# pocopin.net
KiCad netlist of a schematic drawn in Altium Designer
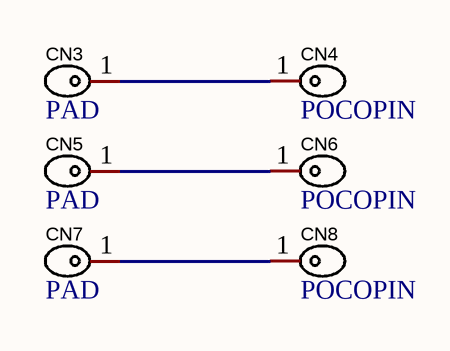
[diagram p0: pocopin.SchDoc]

(export (version "E")
  (design (tool "Eeschema 10.0.6"))
  (components
    (comp (ref "CN3")
      (value "PAD")
      (footprint "PAD")
      (fields (field (name "MANUFACTURER") "YIYUAN(怡远)") (field (name "MANUFACTURER PART") "YTC1P-3015-01"))
      (libsource (lib "Schlib1") (part "PAD"))
    )
    (comp (ref "CN4")
      (value "POCOPIN")
      (footprint "pocopin焊盘")
      (fields (field (name "MANUFACTURER") "YIYUAN(怡远)") (field (name "MANUFACTURER PART") "YTC1P-3015-01"))
      (libsource (lib "Schlib1") (part "POCOPIN"))
    )
    (comp (ref "CN5")
      (value "PAD")
      (footprint "PAD")
      (fields (field (name "MANUFACTURER") "YIYUAN(怡远)") (field (name "MANUFACTURER PART") "YTC1P-3015-01"))
      (libsource (lib "Schlib1") (part "PAD"))
    )
    (comp (ref "CN6")
      (value "POCOPIN")
      (footprint "pocopin焊盘")
      (fields (field (name "MANUFACTURER") "YIYUAN(怡远)") (field (name "MANUFACTURER PART") "YTC1P-3015-01"))
      (libsource (lib "Schlib1") (part "POCOPIN"))
    )
    (comp (ref "CN7")
      (value "PAD")
      (footprint "PAD")
      (fields (field (name "MANUFACTURER") "YIYUAN(怡远)") (field (name "MANUFACTURER PART") "YTC1P-3015-01"))
      (libsource (lib "Schlib1") (part "PAD"))
    )
    (comp (ref "CN8")
      (value "POCOPIN")
      (footprint "pocopin焊盘")
      (fields (field (name "MANUFACTURER") "YIYUAN(怡远)") (field (name "MANUFACTURER PART") "YTC1P-3015-01"))
      (libsource (lib "Schlib1") (part "POCOPIN"))
    )
  )
  (nets
    (net (code "1") (name "Net-(CN3-Pad1)") (class "Default")
      (node (ref "CN3") (pin "1") (pinfunction "1_1") (pintype "passive"))
      (node (ref "CN4") (pin "1") (pinfunction "1_1") (pintype "passive"))
    )
    (net (code "2") (name "Net-(CN5-Pad1)") (class "Default")
      (node (ref "CN5") (pin "1") (pinfunction "1_1") (pintype "passive"))
      (node (ref "CN6") (pin "1") (pinfunction "1_1") (pintype "passive"))
    )
    (net (code "3") (name "Net-(CN7-Pad1)") (class "Default")
      (node (ref "CN7") (pin "1") (pinfunction "1_1") (pintype "passive"))
      (node (ref "CN8") (pin "1") (pinfunction "1_1") (pintype "passive"))
    )
  )
)
